# HAE_Actuators.net
KiCad netlist of a schematic drawn in Altium Designer
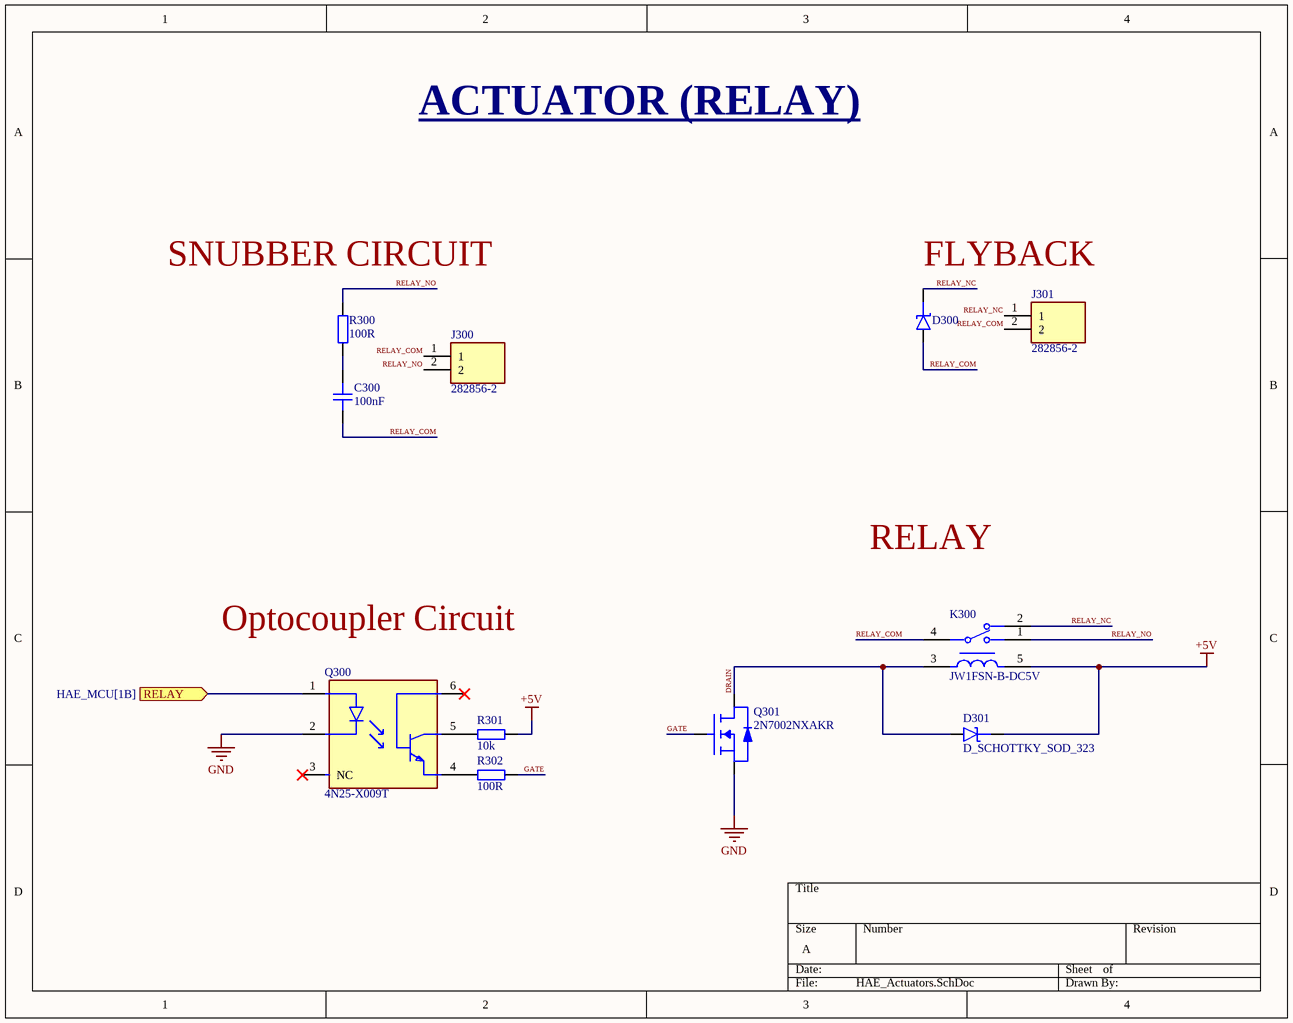
[diagram p0: HAE_Actuators.SchDoc]

(export (version "E")
  (design (tool "Eeschema 10.0.6"))
  (components
    (comp (ref "C300")
      (value "100nF")
      (footprint "CAP_0603")
      (description "Capacitor SMD 0603")
      (libsource (lib "PhilsLab_Library") (part "CAP_0603"))
    )
    (comp (ref "D300")
      (value "D_SCHOTTKY_SOD_323")
      (footprint "SOD-323")
      (description "Diode Schottky SMD SOD-323")
      (libsource (lib "PhilsLab_Library") (part "D_SCHOTTKY_SOD_323"))
    )
    (comp (ref "D301")
      (value "D_SCHOTTKY_SOD_323")
      (footprint "SOD-323")
      (description "Diode Schottky SMD SOD-323")
      (libsource (lib "PhilsLab_Library") (part "D_SCHOTTKY_SOD_323"))
    )
    (comp (ref "J300")
      (value "282856-2")
      (footprint "TE_282856-2")
      (description "TERMI-BLOK PCB MOUNT 2P")
      (fields (field (name "MF") "TE Connectivity"))
      (libsource (lib "Project_1") (part "282856-2"))
    )
    (comp (ref "J301")
      (value "282856-2")
      (footprint "TE_282856-2")
      (description "TERMI-BLOK PCB MOUNT 2P")
      (fields (field (name "MF") "TE Connectivity"))
      (libsource (lib "Project_1") (part "282856-2"))
    )
    (comp (ref "K300")
      (value "JW1FSN-B-DC5V")
      (footprint "FP-JW1FSN-B-DC5V-MFG")
      (description "RELAY GEN PURPOSE SPDT 10A 5V")
      (libsource (lib "Altium Content Vault") (part "9326bfaabe3e5fa933881ff237cda8c"))
    )
    (comp (ref "Q300")
      (value "4N25-X009T")
      (footprint "FP-4N25-X009T-MFG")
      (description "4N25-X009T Optocoupler DC-IN 1-CH Transistor With Base DC-OUT 6-Pin PDIP SMD T/R")
      (libsource (lib "Altium Content Vault") (part "cc3cd645612a37f745648d5741cac6e"))
    )
    (comp (ref "Q301")
      (value "2N7002NXAKR")
      (footprint "SSM3J338R,LF-SOT23-F")
      (description "MOSFET N-Channel Vds=60V Id=300mA with ESD Protection")
      (fields (field (name "MANUFACTURER") "Nexperia"))
      (libsource (lib "PhilsLab_Library") (part "2N7002NXAKR"))
    )
    (comp (ref "R300")
      (value "100R")
      (footprint "RES_0402")
      (description "Resistor SMD 0402")
      (libsource (lib "PhilsLab_Library") (part "RES_0402"))
    )
    (comp (ref "R301")
      (value "10k")
      (footprint "RES_0402")
      (description "Resistor SMD 0402")
      (libsource (lib "PhilsLab_Library") (part "RES_0402"))
    )
    (comp (ref "R302")
      (value "100R")
      (footprint "RES_0402")
      (description "Resistor SMD 0402")
      (libsource (lib "PhilsLab_Library") (part "RES_0402"))
    )
  )
  (nets
    (net (code "1") (name "+5V") (class "Default")
      (node (ref "D301") (pin "K") (pinfunction "K_K") (pintype "passive"))
      (node (ref "K300") (pin "5") (pinfunction "5_5") (pintype "passive"))
      (node (ref "R301") (pin "2") (pinfunction "2_2") (pintype "passive"))
    )
    (net (code "2") (name "/DRAIN") (class "Default")
      (node (ref "D301") (pin "A") (pinfunction "A_A") (pintype "passive"))
      (node (ref "K300") (pin "3") (pinfunction "3_3") (pintype "passive"))
      (node (ref "Q301") (pin "D") (pinfunction "D_D") (pintype "passive"))
    )
    (net (code "3") (name "/GATE") (class "Default")
      (node (ref "Q301") (pin "G") (pinfunction "G_G") (pintype "passive"))
      (node (ref "R302") (pin "2") (pinfunction "2_2") (pintype "passive"))
    )
    (net (code "4") (name "/RELAY") (class "Default")
      (node (ref "Q300") (pin "1") (pinfunction "A_1") (pintype "passive"))
    )
    (net (code "5") (name "/RELAY_COM") (class "Default")
      (node (ref "C300") (pin "1") (pinfunction "1_1") (pintype "passive"))
      (node (ref "D300") (pin "A") (pinfunction "A_A") (pintype "passive"))
      (node (ref "J300") (pin "1") (pinfunction "1_1") (pintype "passive"))
      (node (ref "J301") (pin "2") (pinfunction "2_2") (pintype "passive"))
      (node (ref "K300") (pin "4") (pinfunction "4_4") (pintype "passive"))
    )
    (net (code "6") (name "/RELAY_NC") (class "Default")
      (node (ref "D300") (pin "K") (pinfunction "K_K") (pintype "passive"))
      (node (ref "J301") (pin "1") (pinfunction "1_1") (pintype "passive"))
      (node (ref "K300") (pin "2") (pinfunction "2_2") (pintype "passive"))
    )
    (net (code "7") (name "/RELAY_NO") (class "Default")
      (node (ref "J300") (pin "2") (pinfunction "2_2") (pintype "passive"))
      (node (ref "K300") (pin "1") (pinfunction "1_1") (pintype "passive"))
      (node (ref "R300") (pin "1") (pinfunction "1_1") (pintype "passive"))
    )
    (net (code "8") (name "GND") (class "Default")
      (node (ref "Q300") (pin "2") (pinfunction "C_2") (pintype "passive"))
      (node (ref "Q301") (pin "S") (pinfunction "S_S") (pintype "passive"))
    )
    (net (code "9") (name "Net-(C300-Pad2)") (class "Default")
      (node (ref "C300") (pin "2") (pinfunction "2_2") (pintype "passive"))
      (node (ref "R300") (pin "2") (pinfunction "2_2") (pintype "passive"))
    )
    (net (code "10") (name "Net-(Q300-C-Pad5)") (class "Default")
      (node (ref "Q300") (pin "5") (pinfunction "C_5") (pintype "passive"))
      (node (ref "R301") (pin "1") (pinfunction "1_1") (pintype "passive"))
    )
    (net (code "11") (name "Net-(Q300-E)") (class "Default")
      (node (ref "Q300") (pin "4") (pinfunction "E_4") (pintype "passive"))
      (node (ref "R302") (pin "1") (pinfunction "1_1") (pintype "passive"))
    )
    (net (code "12") (name "unconnected-(Q300-B-Pad6)") (class "Default")
      (node (ref "Q300") (pin "6") (pinfunction "B_6") (pintype "passive+no_connect"))
    )
    (net (code "13") (name "unconnected-(Q300-NC-Pad3)") (class "Default")
      (node (ref "Q300") (pin "3") (pinfunction "NC_3") (pintype "passive+no_connect"))
    )
  )
)
